# htx212_rpi.net
KiCad netlist of a schematic drawn in EAGLE
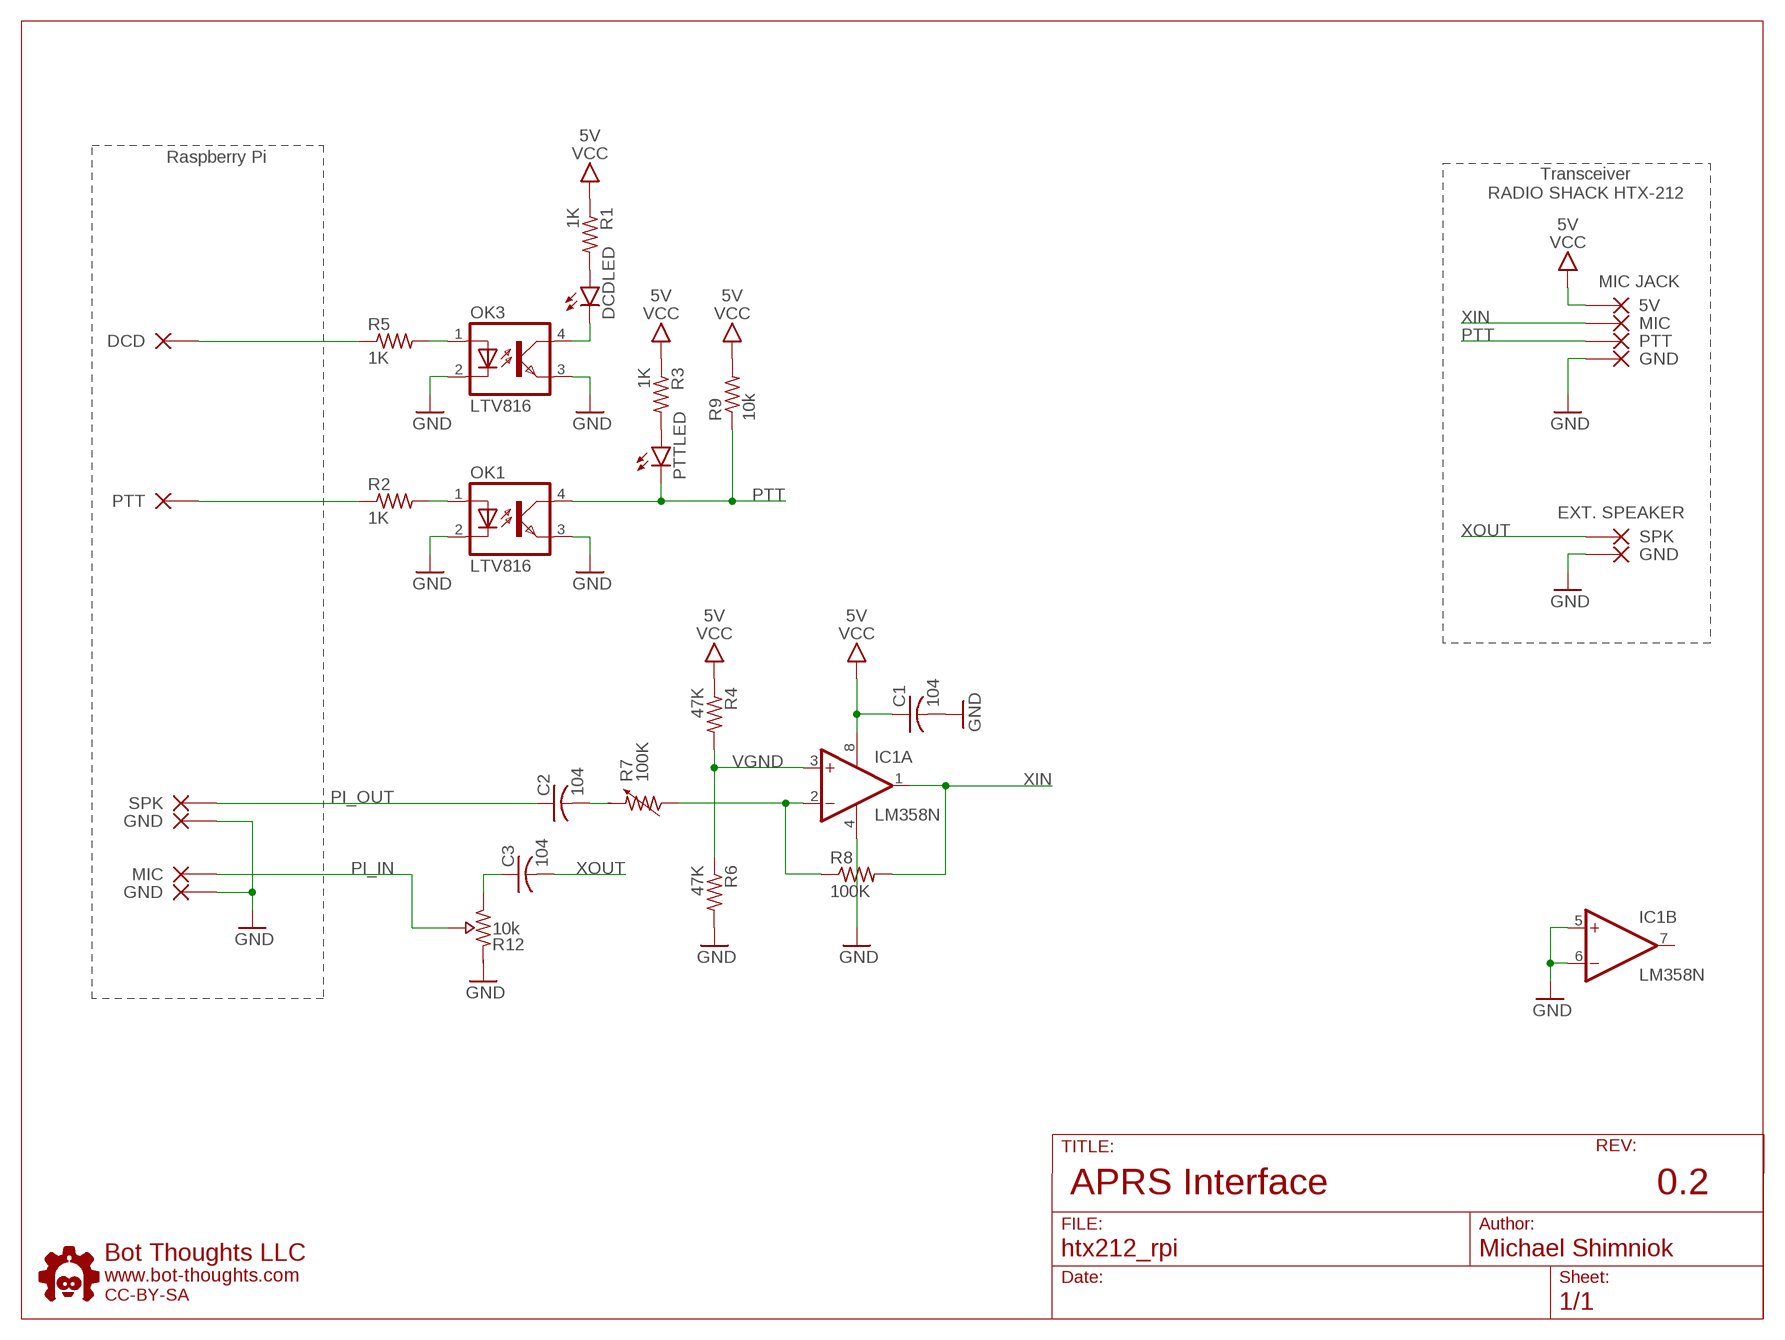
[diagram p0: schematic, sheet 1]

(export (version "E")
  (design (tool "Eeschema 10.0.6"))
  (components
    (comp (ref "C1")
      (value "104")
      (footprint "eagle-import:C075")
      (libsource (lib "eagle-import") (part "C-075PTH"))
    )
    (comp (ref "C2")
      (value "104")
      (footprint "eagle-import:C075")
      (libsource (lib "eagle-import") (part "C-075PTH"))
    )
    (comp (ref "C3")
      (value "104")
      (footprint "eagle-import:C050")
      (libsource (lib "eagle-import") (part "C-050PTH"))
    )
    (comp (ref "DCDLED")
      (value "LED5MMRA")
      (footprint "eagle-import:LED5MMRA")
      (libsource (lib "eagle-import") (part "LED5MMRA"))
    )
    (comp (ref "IC1")
      (value "LM358N")
      (footprint "eagle-import:DIL08")
      (libsource (lib "eagle-import") (part "LM358N"))
    )
    (comp (ref "OK1")
      (value "LTV816")
      (footprint "eagle-import:DIL04")
      (libsource (lib "eagle-import") (part "LTV816"))
    )
    (comp (ref "OK3")
      (value "LTV816")
      (footprint "eagle-import:DIL04")
      (libsource (lib "eagle-import") (part "LTV816"))
    )
    (comp (ref "PTTLED")
      (value "LED5MMRA")
      (footprint "eagle-import:LED5MMRA")
      (libsource (lib "eagle-import") (part "LED5MMRA"))
    )
    (comp (ref "R1")
      (value "1K")
      (footprint "eagle-import:0204_7")
      (libsource (lib "eagle-import") (part "R0204/7-PTH"))
    )
    (comp (ref "R2")
      (value "1K")
      (footprint "eagle-import:0204_7")
      (libsource (lib "eagle-import") (part "R0204/7-PTH"))
    )
    (comp (ref "R3")
      (value "1K")
      (footprint "eagle-import:0204_7")
      (libsource (lib "eagle-import") (part "R0204/7-PTH"))
    )
    (comp (ref "R4")
      (value "47K")
      (footprint "eagle-import:0204_7")
      (libsource (lib "eagle-import") (part "R0204/7-PTH"))
    )
    (comp (ref "R5")
      (value "1K")
      (footprint "eagle-import:0204_7")
      (libsource (lib "eagle-import") (part "R0204/7-PTH"))
    )
    (comp (ref "R6")
      (value "47K")
      (footprint "eagle-import:0204_7")
      (libsource (lib "eagle-import") (part "R0204/7-PTH"))
    )
    (comp (ref "R7")
      (value "100K")
      (footprint "eagle-import:CA6V")
      (libsource (lib "eagle-import") (part "TRIM_2-CA6V"))
    )
    (comp (ref "R8")
      (value "100K")
      (footprint "eagle-import:0204_7")
      (libsource (lib "eagle-import") (part "R0204/7-PTH"))
    )
    (comp (ref "R9")
      (value "10k")
      (footprint "eagle-import:0204_7")
      (libsource (lib "eagle-import") (part "R0204/7-PTH"))
    )
    (comp (ref "R12")
      (value "10k")
      (footprint "eagle-import:CA6V")
      (libsource (lib "eagle-import") (part "TRIM-CA6V"))
    )
    (comp (ref "U$3")
      (value "BTLOGO-LOGO-MD")
      (footprint "eagle-import:BTLOGOM")
      (libsource (lib "eagle-import") (part "BTLOGO-LOGO-MD"))
    )
    (comp (ref "X1")
      (value "MIC")
      (footprint "eagle-import:PAD_22GA")
      (libsource (lib "eagle-import") (part "WIREPAD_22GA"))
    )
    (comp (ref "X2")
      (value "GND")
      (footprint "eagle-import:PAD_22GA")
      (libsource (lib "eagle-import") (part "WIREPAD_22GA"))
    )
    (comp (ref "X3")
      (value "PTT")
      (footprint "eagle-import:PAD_22GA")
      (libsource (lib "eagle-import") (part "WIREPAD_22GA"))
    )
    (comp (ref "X4")
      (value "5V")
      (footprint "eagle-import:PAD_22GA")
      (libsource (lib "eagle-import") (part "WIREPAD_22GA"))
    )
    (comp (ref "X5")
      (value "GND")
      (footprint "eagle-import:PAD_22GA")
      (libsource (lib "eagle-import") (part "WIREPAD_22GA"))
    )
    (comp (ref "X6")
      (value "SPK")
      (footprint "eagle-import:PAD_22GA")
      (libsource (lib "eagle-import") (part "WIREPAD_22GA"))
    )
    (comp (ref "X7")
      (value "MIC")
      (footprint "eagle-import:PAD_22GA")
      (libsource (lib "eagle-import") (part "WIREPAD_22GA"))
    )
    (comp (ref "X8")
      (value "GND")
      (footprint "eagle-import:PAD_22GA")
      (libsource (lib "eagle-import") (part "WIREPAD_22GA"))
    )
    (comp (ref "X9")
      (value "PTT")
      (footprint "eagle-import:PAD_24GA")
      (libsource (lib "eagle-import") (part "WIREPAD_24GA"))
    )
    (comp (ref "X12")
      (value "SPK")
      (footprint "eagle-import:PAD_22GA")
      (libsource (lib "eagle-import") (part "WIREPAD_22GA"))
    )
    (comp (ref "X13")
      (value "GND")
      (footprint "eagle-import:PAD_22GA")
      (libsource (lib "eagle-import") (part "WIREPAD_22GA"))
    )
    (comp (ref "X15")
      (value "DCD")
      (footprint "eagle-import:PAD_24GA")
      (libsource (lib "eagle-import") (part "WIREPAD_24GA"))
    )
  )
  (nets
    (net (code "1") (name "/PI_IN") (class "Default")
      (node (ref "R12") (pin "S") (pinfunction "WIPER_S") (pintype "passive"))
      (node (ref "X7") (pin "P$1") (pinfunction "P_P$1") (pintype "bidirectional"))
    )
    (net (code "2") (name "/PI_OUT") (class "Default")
      (node (ref "C2") (pin "1") (pinfunction "+_1") (pintype "passive"))
      (node (ref "X6") (pin "P$1") (pinfunction "P_P$1") (pintype "bidirectional"))
    )
    (net (code "3") (name "/PTT") (class "Default")
      (node (ref "OK1") (pin "4") (pinfunction "COL_4") (pintype "passive"))
      (node (ref "PTTLED") (pin "C") (pinfunction "C_C") (pintype "passive"))
      (node (ref "R9") (pin "1") (pinfunction "1_1") (pintype "passive"))
      (node (ref "X3") (pin "P$1") (pinfunction "P_P$1") (pintype "bidirectional"))
    )
    (net (code "4") (name "/VGND") (class "Default")
      (node (ref "IC1") (pin "3") (pinfunction "+IN_3") (pintype "input"))
      (node (ref "R4") (pin "2") (pinfunction "2_2") (pintype "passive"))
      (node (ref "R6") (pin "1") (pinfunction "1_1") (pintype "passive"))
    )
    (net (code "5") (name "/XIN") (class "Default")
      (node (ref "IC1") (pin "1") (pinfunction "OUT_1") (pintype "output"))
      (node (ref "R8") (pin "2") (pinfunction "2_2") (pintype "passive"))
      (node (ref "X1") (pin "P$1") (pinfunction "P_P$1") (pintype "bidirectional"))
    )
    (net (code "6") (name "/XOUT") (class "Default")
      (node (ref "C3") (pin "2") (pinfunction "-_2") (pintype "passive"))
      (node (ref "X12") (pin "P$1") (pinfunction "P_P$1") (pintype "bidirectional"))
    )
    (net (code "7") (name "5V") (class "Default")
      (node (ref "C1") (pin "1") (pinfunction "+_1") (pintype "passive"))
      (node (ref "IC1") (pin "8") (pinfunction "V+_8") (pintype "power_in"))
      (node (ref "R1") (pin "1") (pinfunction "1_1") (pintype "passive"))
      (node (ref "R3") (pin "1") (pinfunction "1_1") (pintype "passive"))
      (node (ref "R4") (pin "1") (pinfunction "1_1") (pintype "passive"))
      (node (ref "R9") (pin "2") (pinfunction "2_2") (pintype "passive"))
      (node (ref "X4") (pin "P$1") (pinfunction "P_P$1") (pintype "bidirectional"))
    )
    (net (code "8") (name "GND") (class "Default")
      (node (ref "C1") (pin "2") (pinfunction "-_2") (pintype "passive"))
      (node (ref "IC1") (pin "4") (pinfunction "V-_4") (pintype "power_in"))
      (node (ref "IC1") (pin "5") (pinfunction "+IN_5") (pintype "input"))
      (node (ref "IC1") (pin "6") (pinfunction "-IN_6") (pintype "input"))
      (node (ref "OK1") (pin "2") (pinfunction "C_2") (pintype "passive"))
      (node (ref "OK1") (pin "3") (pinfunction "EMIT_3") (pintype "passive"))
      (node (ref "OK3") (pin "2") (pinfunction "C_2") (pintype "passive"))
      (node (ref "OK3") (pin "3") (pinfunction "EMIT_3") (pintype "passive"))
      (node (ref "R12") (pin "E") (pinfunction "B_E") (pintype "passive"))
      (node (ref "R6") (pin "2") (pinfunction "2_2") (pintype "passive"))
      (node (ref "X13") (pin "P$1") (pinfunction "P_P$1") (pintype "bidirectional"))
      (node (ref "X2") (pin "P$1") (pinfunction "P_P$1") (pintype "bidirectional"))
      (node (ref "X5") (pin "P$1") (pinfunction "P_P$1") (pintype "bidirectional"))
      (node (ref "X8") (pin "P$1") (pinfunction "P_P$1") (pintype "bidirectional"))
    )
    (net (code "9") (name "Net-(C2--)") (class "Default")
      (node (ref "C2") (pin "2") (pinfunction "-_2") (pintype "passive"))
      (node (ref "R7") (pin "E") (pinfunction "B_E") (pintype "passive"))
    )
    (net (code "10") (name "Net-(C3-+)") (class "Default")
      (node (ref "C3") (pin "1") (pinfunction "+_1") (pintype "passive"))
      (node (ref "R12") (pin "A") (pinfunction "A_A") (pintype "passive"))
    )
    (net (code "11") (name "Net-(DCDLED-PadA)") (class "Default")
      (node (ref "DCDLED") (pin "A") (pinfunction "A_A") (pintype "passive"))
      (node (ref "R1") (pin "2") (pinfunction "2_2") (pintype "passive"))
    )
    (net (code "12") (name "Net-(IC1A--IN)") (class "Default")
      (node (ref "IC1") (pin "2") (pinfunction "-IN_2") (pintype "input"))
      (node (ref "R7") (pin "S") (pinfunction "WIPER_S") (pintype "passive"))
      (node (ref "R8") (pin "1") (pinfunction "1_1") (pintype "passive"))
    )
    (net (code "13") (name "Net-(OK1-A)") (class "Default")
      (node (ref "OK1") (pin "1") (pinfunction "A_1") (pintype "passive"))
      (node (ref "R2") (pin "2") (pinfunction "2_2") (pintype "passive"))
    )
    (net (code "14") (name "Net-(OK3-A)") (class "Default")
      (node (ref "OK3") (pin "1") (pinfunction "A_1") (pintype "passive"))
      (node (ref "R5") (pin "2") (pinfunction "2_2") (pintype "passive"))
    )
    (net (code "15") (name "Net-(OK3-COL)") (class "Default")
      (node (ref "DCDLED") (pin "C") (pinfunction "C_C") (pintype "passive"))
      (node (ref "OK3") (pin "4") (pinfunction "COL_4") (pintype "passive"))
    )
    (net (code "16") (name "Net-(PTTLED-PadA)") (class "Default")
      (node (ref "PTTLED") (pin "A") (pinfunction "A_A") (pintype "passive"))
      (node (ref "R3") (pin "2") (pinfunction "2_2") (pintype "passive"))
    )
    (net (code "17") (name "Net-(X9-P)") (class "Default")
      (node (ref "R2") (pin "1") (pinfunction "1_1") (pintype "passive"))
      (node (ref "X9") (pin "P$1") (pinfunction "P_P$1") (pintype "bidirectional"))
    )
    (net (code "18") (name "Net-(X15-P)") (class "Default")
      (node (ref "R5") (pin "1") (pinfunction "1_1") (pintype "passive"))
      (node (ref "X15") (pin "P$1") (pinfunction "P_P$1") (pintype "bidirectional"))
    )
    (net (code "19") (name "unconnected-(IC1B-OUT-Pad7)") (class "Default")
      (node (ref "IC1") (pin "7") (pinfunction "OUT_7") (pintype "output"))
    )
  )
)
